# DCDC_pump.net
KiCad netlist of a schematic drawn in Altium Designer
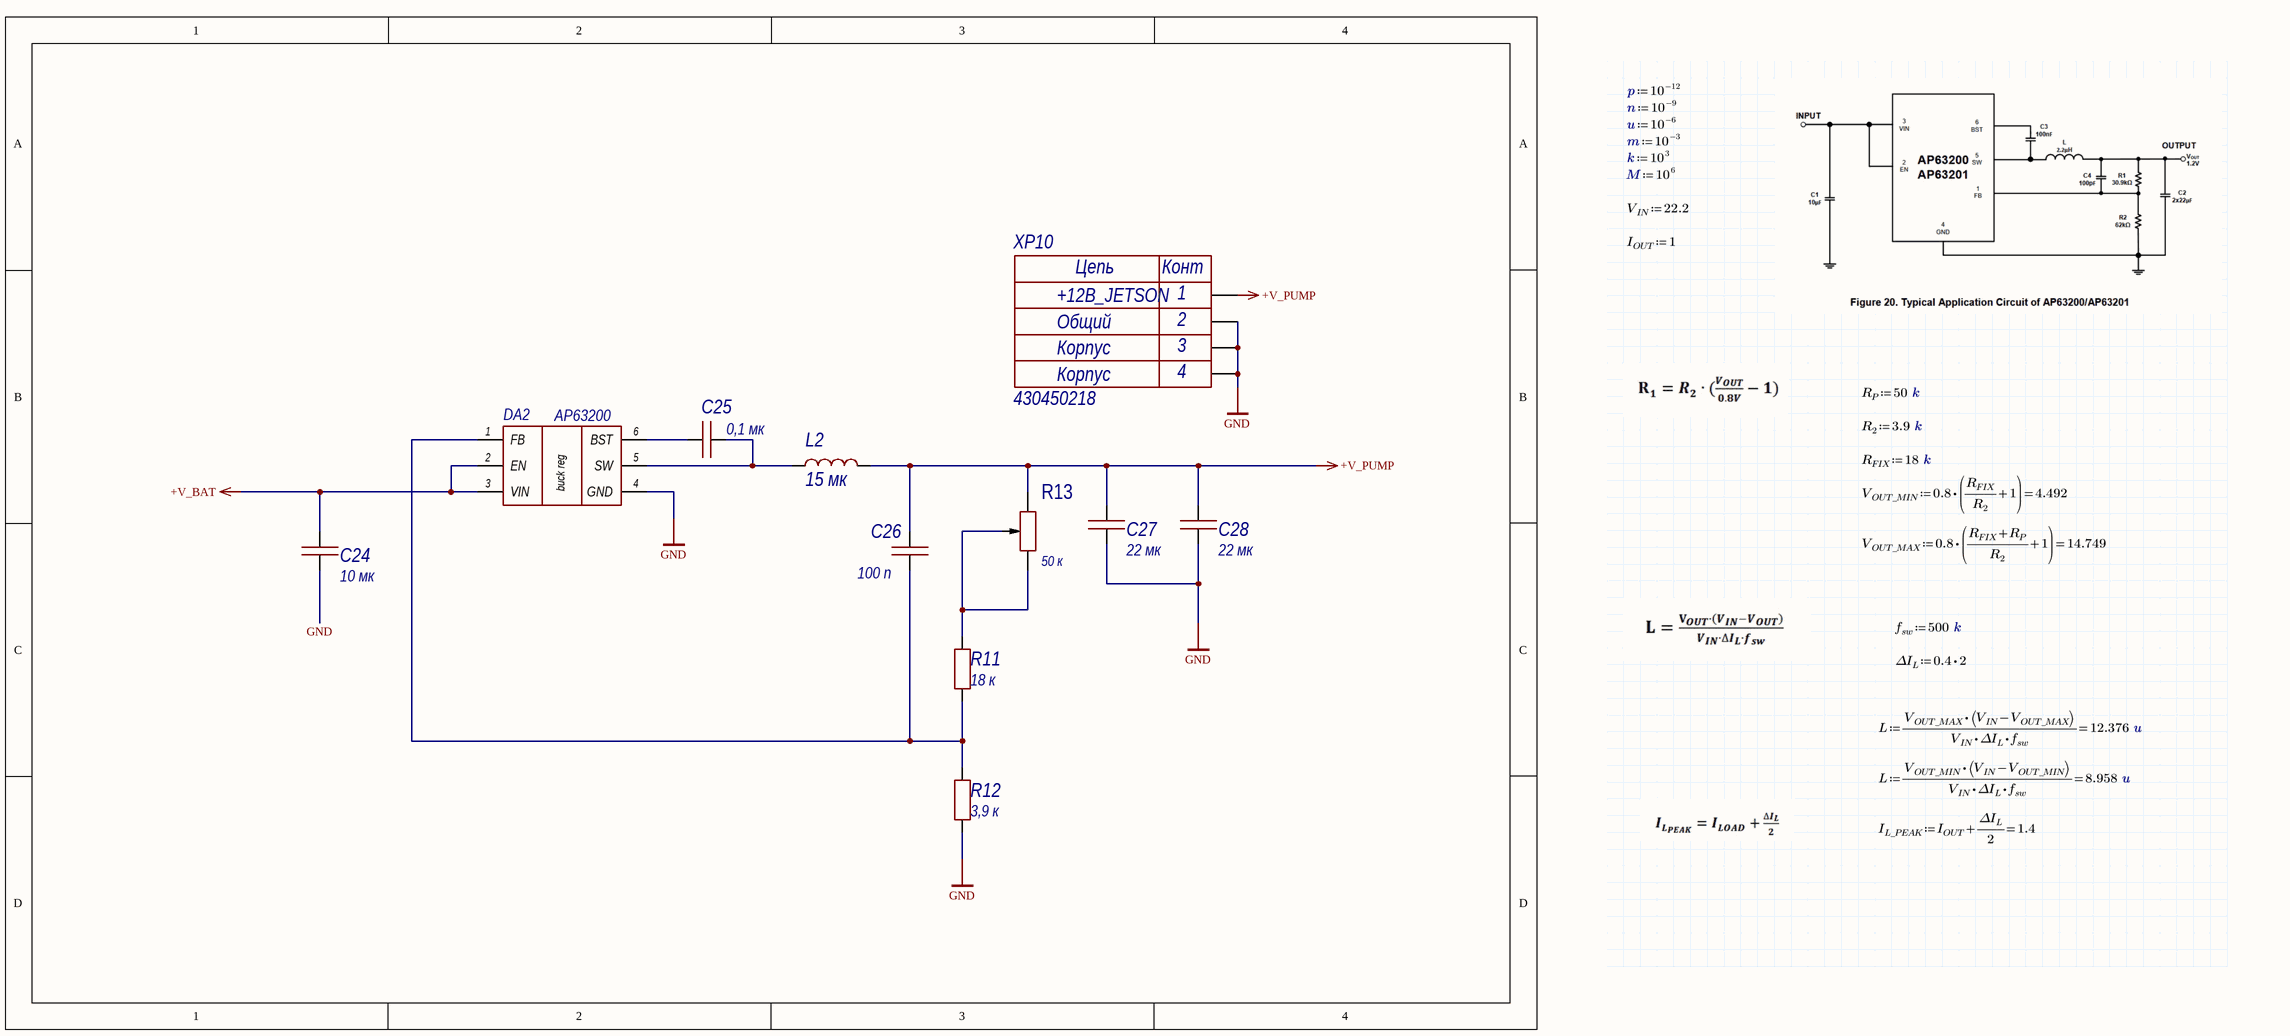
[diagram p0: DCDC_pump.SchDoc]

(export (version "E")
  (design (tool "Eeschema 10.0.6"))
  (components
    (comp (ref "C24")
      (value "10 мк")
      (footprint "1210C")
      (description "Конденсатор")
      (fields (field (name "PART NUMBER") "Capacitor_10u_10_35V_X7R_1210C") (field (name "TOLERANCE") "0,1"))
      (libsource (lib "Hydrolib") (part "Capacitor"))
    )
    (comp (ref "C25")
      (value "0,1 мк")
      (footprint "0603C")
      (description "Конденсатор")
      (fields (field (name "PART NUMBER") "Capacitor_0,1u_10_50V_X7R_0603C") (field (name "TOLERANCE") "0,1"))
      (libsource (lib "Hydrolib") (part "Capacitor"))
    )
    (comp (ref "C26")
      (value "100 п")
      (footprint "0603C")
      (description "Конденсатор")
      (fields (field (name "PART NUMBER") "Capacitor_100p_10_50V_X7R_0603C") (field (name "TOLERANCE") "0,1"))
      (libsource (lib "Hydrolib") (part "Capacitor"))
    )
    (comp (ref "C27")
      (value "22 мк")
      (footprint "1210C")
      (description "Конденсатор")
      (fields (field (name "PART NUMBER") "Capacitor_22u_10_25V_X7R_1210C") (field (name "TOLERANCE") "0,1"))
      (libsource (lib "Hydrolib") (part "Capacitor"))
    )
    (comp (ref "C28")
      (value "22 мк")
      (footprint "1210C")
      (description "Конденсатор")
      (fields (field (name "PART NUMBER") "Capacitor_22u_10_25V_X7R_1210C") (field (name "TOLERANCE") "0,1"))
      (libsource (lib "Hydrolib") (part "Capacitor"))
    )
    (comp (ref "DA2")
      (value "AP63200")
      (footprint "TSOT26")
      (description "DC-DC понижающий преобразователь, Vin: 3.8 - 40 В, adj, 2 А")
      (libsource (lib "Hydrolib") (part "AP63200"))
    )
    (comp (ref "L2")
      (value "15 мк")
      (footprint "SP43")
      (description "Индуктивность на 15 мкГн, номинальный ток 1,3 А")
      (fields (field (name "PART NUMBER") "SP43-150K"))
      (libsource (lib "Hydrolib") (part "Inductance"))
    )
    (comp (ref "R11")
      (value "18 к")
      (footprint "0603R")
      (description "Резистор номиналом 18 кОм и точностью 1%")
      (fields (field (name "PART NUMBER") "Resistor_18k_1_0603") (field (name "TOLERANCE") "1%"))
      (libsource (lib "Hydrolib") (part "Resistor"))
    )
    (comp (ref "R12")
      (value "3,9 к")
      (footprint "0603R")
      (description "Резистор номиналом 3,9 кОм и точностью 1%")
      (fields (field (name "PART NUMBER") "Resistor_3.9k_1_0603") (field (name "TOLERANCE") "1%"))
      (libsource (lib "Hydrolib") (part "Resistor"))
    )
    (comp (ref "R13")
      (value "50 к")
      (footprint "3mm_trim")
      (description "Потенциометр однооборотный керметный 50кОм 0.1Вт ±25% SMD лента на катушке")
      (fields (field (name "PART NUMBER") "TC33X-2-503E") (field (name "TOLERANCE") "50%"))
      (libsource (lib "Hydrolib") (part "trim_res"))
    )
    (comp (ref "XP10")
      (value "430450218")
      (footprint "Molex_430450218")
      (fields
        (field (name "VALUE3") "Корпус")
        (field (name "VALUE2") "Общий")
        (field (name "VALUE4") "Корпус")
        (field (name "VALUE1") "+12В_JETSON")
        (field (name "PART NUMBER") "Molex_430450218")
      )
      (libsource (lib "Hydrolib") (part "Molex_430450218"))
    )
  )
  (nets
    (net (code "1") (name "+V_BAT") (class "Default")
      (node (ref "C24") (pin "2") (pinfunction "2_2") (pintype "passive"))
      (node (ref "DA2") (pin "2") (pinfunction "EN_2") (pintype "passive"))
      (node (ref "DA2") (pin "3") (pinfunction "VIN_3") (pintype "passive"))
    )
    (net (code "2") (name "+V_PUMP") (class "Default")
      (node (ref "C26") (pin "2") (pinfunction "2_2") (pintype "passive"))
      (node (ref "C27") (pin "2") (pinfunction "2_2") (pintype "passive"))
      (node (ref "C28") (pin "2") (pinfunction "2_2") (pintype "passive"))
      (node (ref "L2") (pin "2") (pinfunction "2_2") (pintype "passive"))
      (node (ref "R13") (pin "3") (pinfunction "3_3") (pintype "passive"))
      (node (ref "XP10") (pin "1") (pinfunction "1_1") (pintype "passive"))
    )
    (net (code "3") (name "GND") (class "Default")
      (node (ref "C24") (pin "1") (pinfunction "1_1") (pintype "passive"))
      (node (ref "C27") (pin "1") (pinfunction "1_1") (pintype "passive"))
      (node (ref "C28") (pin "1") (pinfunction "1_1") (pintype "passive"))
      (node (ref "DA2") (pin "4") (pinfunction "GND_4") (pintype "passive"))
      (node (ref "R12") (pin "1") (pinfunction "1_1") (pintype "passive"))
      (node (ref "XP10") (pin "0") (pinfunction "0_0") (pintype "passive"))
      (node (ref "XP10") (pin "2") (pinfunction "2_2") (pintype "passive"))
    )
    (net (code "4") (name "Net-(DA2-BST)") (class "Default")
      (node (ref "C25") (pin "1") (pinfunction "1_1") (pintype "passive"))
      (node (ref "DA2") (pin "6") (pinfunction "BST_6") (pintype "passive"))
    )
    (net (code "5") (name "Net-(DA2-FB)") (class "Default")
      (node (ref "C26") (pin "1") (pinfunction "1_1") (pintype "passive"))
      (node (ref "DA2") (pin "1") (pinfunction "FB_1") (pintype "passive"))
      (node (ref "R11") (pin "1") (pinfunction "1_1") (pintype "passive"))
      (node (ref "R12") (pin "2") (pinfunction "2_2") (pintype "passive"))
    )
    (net (code "6") (name "Net-(DA2-SW)") (class "Default")
      (node (ref "C25") (pin "2") (pinfunction "2_2") (pintype "passive"))
      (node (ref "DA2") (pin "5") (pinfunction "SW_5") (pintype "passive"))
      (node (ref "L2") (pin "1") (pinfunction "1_1") (pintype "passive"))
    )
    (net (code "7") (name "Net-(R11-Pad2)") (class "Default")
      (node (ref "R11") (pin "2") (pinfunction "2_2") (pintype "passive"))
      (node (ref "R13") (pin "1") (pinfunction "1_1") (pintype "passive"))
      (node (ref "R13") (pin "2") (pinfunction "2_2") (pintype "passive"))
    )
  )
)
